# Usb.net
KiCad netlist of a schematic drawn in Altium Designer
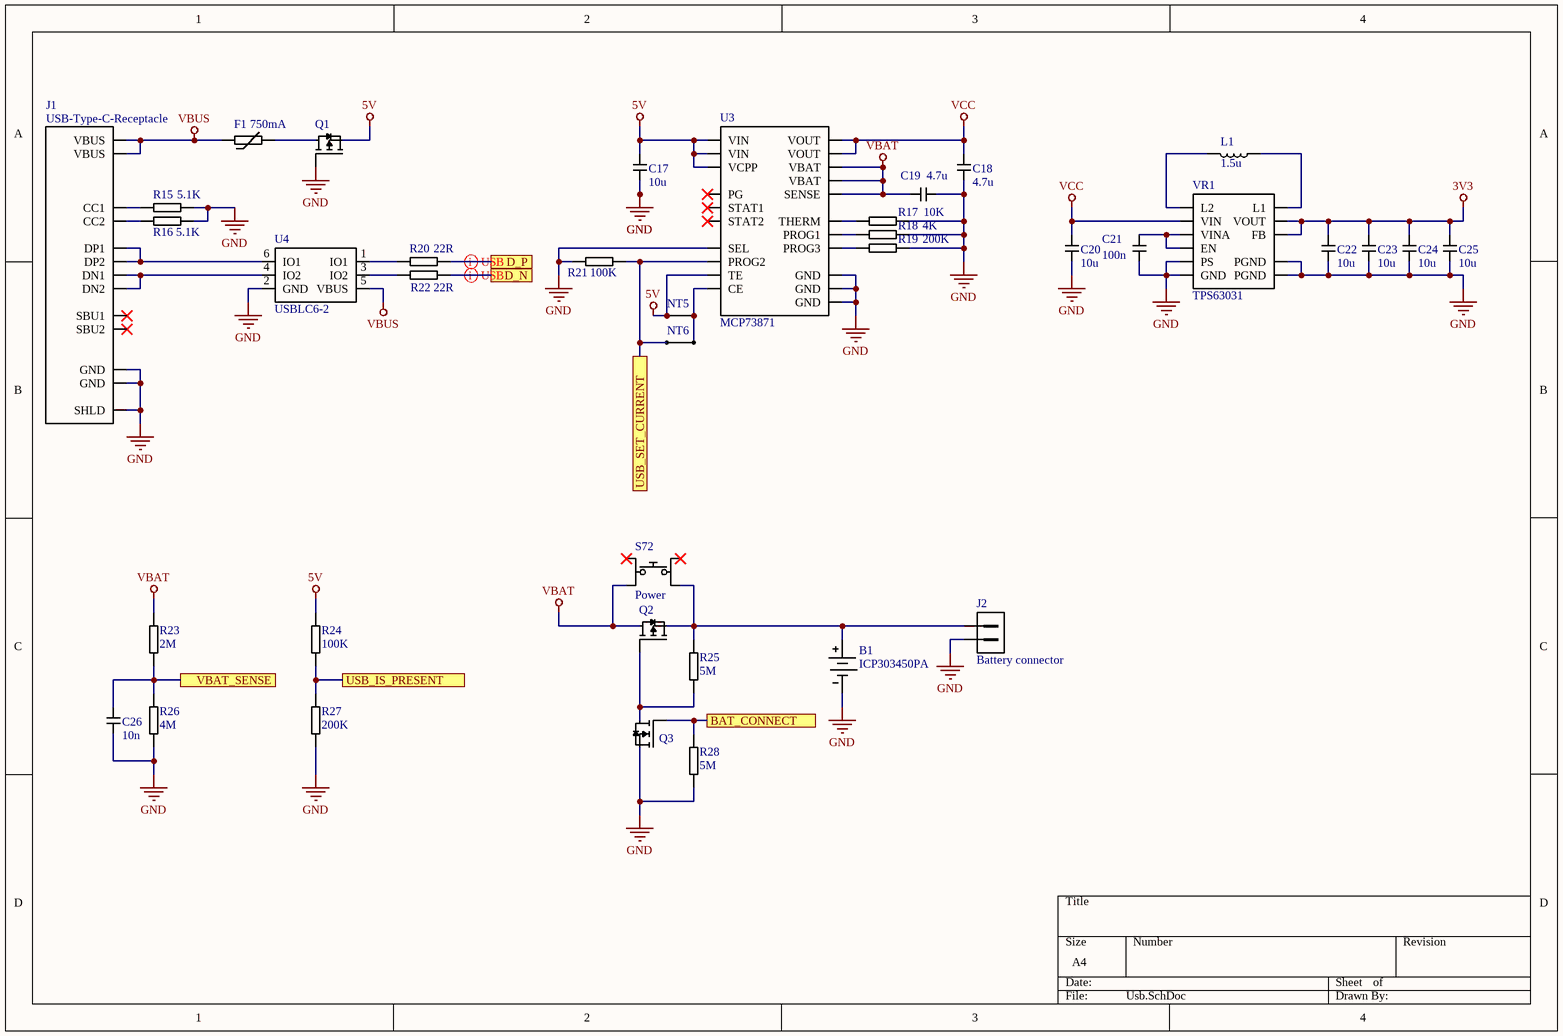
[diagram p0: Usb.SchDoc]

(export (version "E")
  (design (tool "Eeschema 10.0.6"))
  (components
    (comp (ref "B1") (value "ICP303450PA") (libsource (lib "NautilusKB") (part "Battery")))
    (comp (ref "C17")
      (value "10u")
      (footprint "Capacitor_0603")
      (libsource (lib "NautilusKB") (part "Capacitor"))
    )
    (comp (ref "C18")
      (value "4.7u")
      (footprint "Capacitor_0603")
      (libsource (lib "NautilusKB") (part "Capacitor"))
    )
    (comp (ref "C19")
      (value "4.7u")
      (footprint "Capacitor_0603")
      (libsource (lib "NautilusKB") (part "Capacitor"))
    )
    (comp (ref "C20")
      (value "10u")
      (footprint "Capacitor_0603")
      (libsource (lib "NautilusKB") (part "Capacitor"))
    )
    (comp (ref "C21")
      (value "100n")
      (footprint "Capacitor_0603")
      (libsource (lib "NautilusKB") (part "Capacitor"))
    )
    (comp (ref "C22")
      (value "10u")
      (footprint "Capacitor_0603")
      (libsource (lib "NautilusKB") (part "Capacitor"))
    )
    (comp (ref "C23")
      (value "10u")
      (footprint "Capacitor_0603")
      (libsource (lib "NautilusKB") (part "Capacitor"))
    )
    (comp (ref "C24")
      (value "10u")
      (footprint "Capacitor_0603")
      (libsource (lib "NautilusKB") (part "Capacitor"))
    )
    (comp (ref "C25")
      (value "10u")
      (footprint "Capacitor_0603")
      (libsource (lib "NautilusKB") (part "Capacitor"))
    )
    (comp (ref "C26")
      (value "10n")
      (footprint "Capacitor_0603")
      (libsource (lib "NautilusKB") (part "Capacitor"))
    )
    (comp (ref "F1") (value "750mA") (footprint "Resistor_0805") (libsource (lib "NautilusKB") (part "Fuse")))
    (comp (ref "J1")
      (value "USB-Type-C-Receptacle")
      (footprint "TYPE_C_31_M_12")
      (libsource (lib "NautilusKB") (part "USB-Type-C-Receptacle"))
    )
    (comp (ref "J2")
      (value "Battery connector")
      (footprint "JST_SH_2P_Female")
      (libsource (lib "NautilusKB") (part "Connector_2P"))
    )
    (comp (ref "L1")
      (value "1.5u")
      (footprint "Inductor_3015")
      (libsource (lib "NautilusKB") (part "Inductor"))
    )
    (comp (ref "NT5")
      (value "Net tie")
      (footprint "Resistor_0603")
      (libsource (lib "NautilusKB") (part "Net tie"))
    )
    (comp (ref "NT6")
      (value "Net tie")
      (footprint "Resistor_0603")
      (libsource (lib "NautilusKB") (part "Net tie"))
    )
    (comp (ref "Q1") (value "PMOS") (footprint "SOT_233") (libsource (lib "NautilusKB") (part "PMOS")))
    (comp (ref "Q2") (value "PMOS") (footprint "SOT_233") (libsource (lib "NautilusKB") (part "PMOS")))
    (comp (ref "Q3") (value "NMOS") (footprint "SOT_233") (libsource (lib "NautilusKB") (part "NMOS")))
    (comp (ref "R15")
      (value "5.1K")
      (footprint "Resistor_0603")
      (libsource (lib "NautilusKB") (part "Resistor"))
    )
    (comp (ref "R16")
      (value "5.1K")
      (footprint "Resistor_0603")
      (libsource (lib "NautilusKB") (part "Resistor"))
    )
    (comp (ref "R17")
      (value "10K")
      (footprint "Resistor_0603")
      (libsource (lib "NautilusKB") (part "Resistor"))
    )
    (comp (ref "R18")
      (value "4K")
      (footprint "Resistor_0603")
      (libsource (lib "NautilusKB") (part "Resistor"))
    )
    (comp (ref "R19")
      (value "200K")
      (footprint "Resistor_0603")
      (libsource (lib "NautilusKB") (part "Resistor"))
    )
    (comp (ref "R20")
      (value "22R")
      (footprint "Resistor_0603")
      (libsource (lib "NautilusKB") (part "Resistor"))
    )
    (comp (ref "R21")
      (value "100K")
      (footprint "Resistor_0603")
      (libsource (lib "NautilusKB") (part "Resistor"))
    )
    (comp (ref "R22")
      (value "22R")
      (footprint "Resistor_0603")
      (libsource (lib "NautilusKB") (part "Resistor"))
    )
    (comp (ref "R23")
      (value "2M")
      (footprint "Resistor_0603")
      (libsource (lib "NautilusKB") (part "Resistor"))
    )
    (comp (ref "R24")
      (value "100K")
      (footprint "Resistor_0603")
      (libsource (lib "NautilusKB") (part "Resistor"))
    )
    (comp (ref "R25")
      (value "5M")
      (footprint "Resistor_0603")
      (libsource (lib "NautilusKB") (part "Resistor"))
    )
    (comp (ref "R26")
      (value "4M")
      (footprint "Resistor_0603")
      (libsource (lib "NautilusKB") (part "Resistor"))
    )
    (comp (ref "R27")
      (value "200K")
      (footprint "Resistor_0603")
      (libsource (lib "NautilusKB") (part "Resistor"))
    )
    (comp (ref "R28")
      (value "5M")
      (footprint "Resistor_0603")
      (libsource (lib "NautilusKB") (part "Resistor"))
    )
    (comp (ref "S72")
      (value "Power")
      (footprint "Tactile_switch_5.1x5.1mm_4P")
      (libsource (lib "NautilusKB") (part "Pushbutton_4P"))
    )
    (comp (ref "U3")
      (value "MCP73871")
      (footprint "QFN_20_4mm")
      (libsource (lib "NautilusKB") (part "MCP73871"))
    )
    (comp (ref "U4")
      (value "USBLC6-2")
      (footprint "SOT_666")
      (libsource (lib "NautilusKB") (part "USBLC6-2"))
    )
    (comp (ref "VR1")
      (value "TPS63031")
      (footprint "WSON_10_2.6mm")
      (libsource (lib "NautilusKB") (part "TPS63031"))
    )
  )
  (nets
    (net (code "1") (name "/BAT_CONNECT") (class "Default")
      (node (ref "Q3") (pin "1") (pintype "passive"))
      (node (ref "R28") (pin "2") (pintype "passive"))
    )
    (net (code "2") (name "/D_N") (class "Default") (node (ref "R22") (pin "2") (pintype "passive")))
    (net (code "3") (name "/D_P") (class "Default") (node (ref "R20") (pin "2") (pintype "passive")))
    (net (code "4") (name "/USB_IS_PRESENT") (class "Default")
      (node (ref "R24") (pin "1") (pintype "passive"))
      (node (ref "R27") (pin "2") (pintype "passive"))
    )
    (net (code "5") (name "/USB_SET_CURRENT") (class "Default")
      (node (ref "NT6") (pin "1") (pintype "passive"))
      (node (ref "R21") (pin "2") (pintype "passive"))
      (node (ref "U3") (pin "4") (pinfunction "PROG2_4") (pintype "passive"))
    )
    (net (code "6") (name "/VBAT_SENSE") (class "Default")
      (node (ref "C26") (pin "2") (pintype "passive"))
      (node (ref "R23") (pin "1") (pintype "passive"))
      (node (ref "R26") (pin "2") (pintype "passive"))
    )
    (net (code "7") (name "3V3") (class "Default")
      (node (ref "C22") (pin "2") (pintype "passive"))
      (node (ref "C23") (pin "2") (pintype "passive"))
      (node (ref "C24") (pin "2") (pintype "passive"))
      (node (ref "C25") (pin "2") (pintype "passive"))
      (node (ref "VR1") (pin "1") (pinfunction "VOUT_1") (pintype "passive"))
      (node (ref "VR1") (pin "10") (pinfunction "FB_10") (pintype "passive"))
    )
    (net (code "8") (name "5V") (class "Default")
      (node (ref "C17") (pin "2") (pintype "passive"))
      (node (ref "NT5") (pin "1") (pintype "passive"))
      (node (ref "Q1") (pin "2") (pintype "passive"))
      (node (ref "R24") (pin "2") (pintype "passive"))
      (node (ref "U3") (pin "18") (pinfunction "VIN_18") (pintype "passive"))
      (node (ref "U3") (pin "19") (pinfunction "VIN_19") (pintype "passive"))
      (node (ref "U3") (pin "2") (pinfunction "VCPP_2") (pintype "passive"))
      (node (ref "U3") (pin "9") (pinfunction "TE_9") (pintype "passive"))
    )
    (net (code "9") (name "GND") (class "Default")
      (node (ref "B1") (pin "2") (pintype "passive"))
      (node (ref "C17") (pin "1") (pintype "passive"))
      (node (ref "C18") (pin "1") (pintype "passive"))
      (node (ref "C19") (pin "2") (pintype "passive"))
      (node (ref "C20") (pin "1") (pintype "passive"))
      (node (ref "C21") (pin "1") (pintype "passive"))
      (node (ref "C22") (pin "1") (pintype "passive"))
      (node (ref "C23") (pin "1") (pintype "passive"))
      (node (ref "C24") (pin "1") (pintype "passive"))
      (node (ref "C25") (pin "1") (pintype "passive"))
      (node (ref "C26") (pin "1") (pintype "passive"))
      (node (ref "J1") (pin "A1") (pinfunction "GND_A1") (pintype "passive"))
      (node (ref "J1") (pin "B1") (pinfunction "GND_B1") (pintype "passive"))
      (node (ref "J1") (pin "SHLD") (pinfunction "SHLD_SHLD") (pintype "passive"))
      (node (ref "J2") (pin "2") (pintype "passive"))
      (node (ref "Q1") (pin "1") (pintype "passive"))
      (node (ref "Q3") (pin "2") (pintype "passive"))
      (node (ref "R15") (pin "2") (pintype "passive"))
      (node (ref "R16") (pin "2") (pintype "passive"))
      (node (ref "R17") (pin "2") (pintype "passive"))
      (node (ref "R18") (pin "2") (pintype "passive"))
      (node (ref "R19") (pin "2") (pintype "passive"))
      (node (ref "R21") (pin "1") (pintype "passive"))
      (node (ref "R26") (pin "1") (pintype "passive"))
      (node (ref "R27") (pin "1") (pintype "passive"))
      (node (ref "R28") (pin "1") (pintype "passive"))
      (node (ref "U3") (pin "10") (pinfunction "GND_10") (pintype "passive"))
      (node (ref "U3") (pin "11") (pinfunction "GND_11") (pintype "passive"))
      (node (ref "U3") (pin "21") (pinfunction "GND_21") (pintype "passive"))
      (node (ref "U3") (pin "3") (pinfunction "SEL_3") (pintype "passive"))
      (node (ref "U4") (pin "2") (pinfunction "GND_2") (pintype "passive"))
      (node (ref "VR1") (pin "11") (pinfunction "PGND_11") (pintype "passive"))
      (node (ref "VR1") (pin "3") (pinfunction "PGND_3") (pintype "passive"))
      (node (ref "VR1") (pin "7") (pinfunction "PS_7") (pintype "passive"))
      (node (ref "VR1") (pin "9") (pinfunction "GND_9") (pintype "passive"))
    )
    (net (code "10") (name "Net-(B1-Pad1)") (class "Default")
      (node (ref "B1") (pin "1") (pintype "passive"))
      (node (ref "J2") (pin "1") (pintype "passive"))
      (node (ref "Q2") (pin "2") (pintype "passive"))
      (node (ref "R25") (pin "2") (pintype "passive"))
      (node (ref "S72") (pin "2") (pintype "passive"))
    )
    (net (code "11") (name "Net-(F1-Pad2)") (class "Default")
      (node (ref "F1") (pin "2") (pintype "passive"))
      (node (ref "Q1") (pin "3") (pintype "passive"))
    )
    (net (code "12") (name "Net-(J1-CC1)") (class "Default")
      (node (ref "J1") (pin "A5") (pinfunction "CC1_A5") (pintype "passive"))
      (node (ref "R15") (pin "1") (pintype "passive"))
    )
    (net (code "13") (name "Net-(J1-CC2)") (class "Default")
      (node (ref "J1") (pin "B5") (pinfunction "CC2_B5") (pintype "passive"))
      (node (ref "R16") (pin "1") (pintype "passive"))
    )
    (net (code "14") (name "Net-(J1-DN1)") (class "Default")
      (node (ref "J1") (pin "A7") (pinfunction "DN1_A7") (pintype "passive"))
      (node (ref "J1") (pin "B7") (pinfunction "DN2_B7") (pintype "passive"))
      (node (ref "U4") (pin "4") (pinfunction "IO2_4") (pintype "passive"))
    )
    (net (code "15") (name "Net-(J1-DP1)") (class "Default")
      (node (ref "J1") (pin "A6") (pinfunction "DP1_A6") (pintype "passive"))
      (node (ref "J1") (pin "B6") (pinfunction "DP2_B6") (pintype "passive"))
      (node (ref "U4") (pin "6") (pinfunction "IO1_6") (pintype "passive"))
    )
    (net (code "16") (name "Net-(Q2-Pad1)") (class "Default")
      (node (ref "Q2") (pin "1") (pintype "passive"))
      (node (ref "Q3") (pin "3") (pintype "passive"))
      (node (ref "R25") (pin "1") (pintype "passive"))
    )
    (net (code "17") (name "Net-(R20-Pad1)") (class "Default")
      (node (ref "R20") (pin "1") (pintype "passive"))
      (node (ref "U4") (pin "1") (pinfunction "IO1_1") (pintype "passive"))
    )
    (net (code "18") (name "Net-(R22-Pad1)") (class "Default")
      (node (ref "R22") (pin "1") (pintype "passive"))
      (node (ref "U4") (pin "3") (pinfunction "IO2_3") (pintype "passive"))
    )
    (net (code "19") (name "Net-(U3-CE)") (class "Default")
      (node (ref "NT5") (pin "2") (pintype "passive"))
      (node (ref "NT6") (pin "2") (pintype "passive"))
      (node (ref "U3") (pin "17") (pinfunction "CE_17") (pintype "passive"))
    )
    (net (code "20") (name "Net-(U3-PROG1)") (class "Default")
      (node (ref "R18") (pin "1") (pintype "passive"))
      (node (ref "U3") (pin "13") (pinfunction "PROG1_13") (pintype "passive"))
    )
    (net (code "21") (name "Net-(U3-PROG3)") (class "Default")
      (node (ref "R19") (pin "1") (pintype "passive"))
      (node (ref "U3") (pin "12") (pinfunction "PROG3_12") (pintype "passive"))
    )
    (net (code "22") (name "Net-(U3-THERM)") (class "Default")
      (node (ref "R17") (pin "1") (pintype "passive"))
      (node (ref "U3") (pin "5") (pinfunction "THERM_5") (pintype "passive"))
    )
    (net (code "23") (name "Net-(VR1-EN)") (class "Default")
      (node (ref "C21") (pin "2") (pintype "passive"))
      (node (ref "VR1") (pin "6") (pinfunction "EN_6") (pintype "passive"))
      (node (ref "VR1") (pin "8") (pinfunction "VINA_8") (pintype "passive"))
    )
    (net (code "24") (name "Net-(VR1-L1)") (class "Default")
      (node (ref "L1") (pin "2") (pintype "passive"))
      (node (ref "VR1") (pin "4") (pinfunction "L1_4") (pintype "passive"))
    )
    (net (code "25") (name "Net-(VR1-L2)") (class "Default")
      (node (ref "L1") (pin "1") (pintype "passive"))
      (node (ref "VR1") (pin "2") (pinfunction "L2_2") (pintype "passive"))
    )
    (net (code "26") (name "VBAT") (class "Default")
      (node (ref "C19") (pin "1") (pintype "passive"))
      (node (ref "Q2") (pin "3") (pintype "passive"))
      (node (ref "R23") (pin "2") (pintype "passive"))
      (node (ref "S72") (pin "4") (pintype "passive"))
      (node (ref "U3") (pin "14") (pinfunction "VBAT_14") (pintype "passive"))
      (node (ref "U3") (pin "15") (pinfunction "VBAT_15") (pintype "passive"))
      (node (ref "U3") (pin "16") (pinfunction "SENSE_16") (pintype "passive"))
    )
    (net (code "27") (name "VBUS") (class "Default")
      (node (ref "F1") (pin "1") (pintype "passive"))
      (node (ref "J1") (pin "A4") (pinfunction "VBUS_A4") (pintype "passive"))
      (node (ref "J1") (pin "B4") (pinfunction "VBUS_B4") (pintype "passive"))
      (node (ref "U4") (pin "5") (pinfunction "VBUS_5") (pintype "passive"))
    )
    (net (code "28") (name "VCC") (class "Default")
      (node (ref "C18") (pin "2") (pintype "passive"))
      (node (ref "C20") (pin "2") (pintype "passive"))
      (node (ref "U3") (pin "1") (pinfunction "VOUT_1") (pintype "passive"))
      (node (ref "U3") (pin "20") (pinfunction "VOUT_20") (pintype "passive"))
      (node (ref "VR1") (pin "5") (pinfunction "VIN_5") (pintype "passive"))
    )
    (net (code "29") (name "unconnected-(J1-SBU1-PadA8)") (class "Default")
      (node (ref "J1") (pin "A8") (pinfunction "SBU1_A8") (pintype "passive+no_connect"))
    )
    (net (code "30") (name "unconnected-(J1-SBU2-PadB8)") (class "Default")
      (node (ref "J1") (pin "B8") (pinfunction "SBU2_B8") (pintype "passive+no_connect"))
    )
    (net (code "31") (name "unconnected-(S72-Pad1)") (class "Default")
      (node (ref "S72") (pin "1") (pintype "passive+no_connect"))
    )
    (net (code "32") (name "unconnected-(S72-Pad3)") (class "Default")
      (node (ref "S72") (pin "3") (pintype "passive+no_connect"))
    )
    (net (code "33") (name "unconnected-(U3-PG-Pad6)") (class "Default")
      (node (ref "U3") (pin "6") (pinfunction "PG_6") (pintype "passive+no_connect"))
    )
    (net (code "34") (name "unconnected-(U3-STAT1-Pad8)") (class "Default")
      (node (ref "U3") (pin "8") (pinfunction "STAT1_8") (pintype "passive+no_connect"))
    )
    (net (code "35") (name "unconnected-(U3-STAT2-Pad7)") (class "Default")
      (node (ref "U3") (pin "7") (pinfunction "STAT2_7") (pintype "passive+no_connect"))
    )
  )
)
